# peripherals.net
KiCad netlist of a schematic drawn in Altium Designer
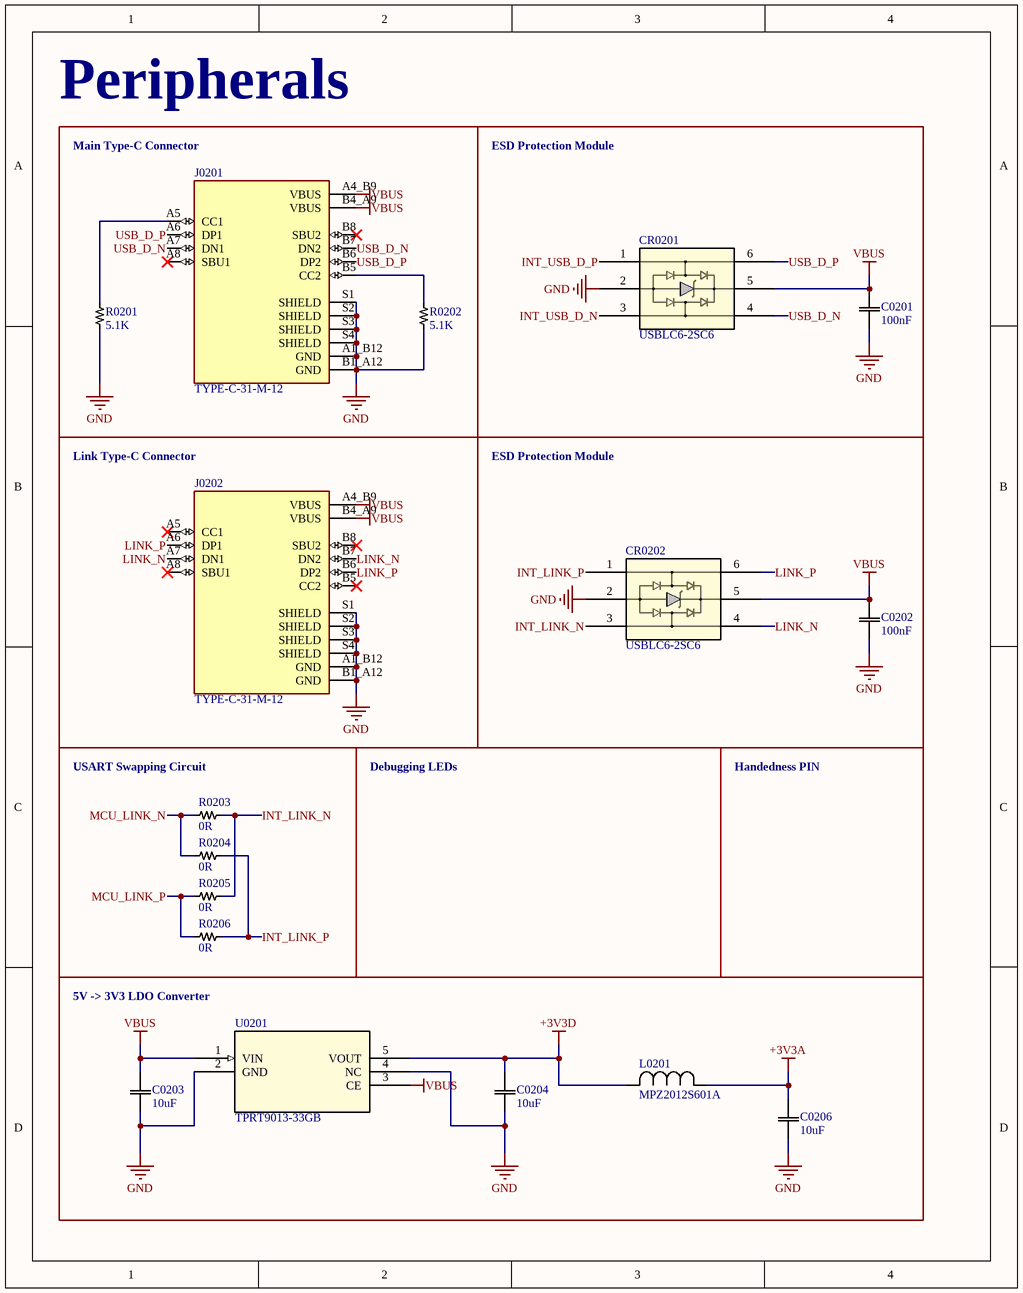
[diagram p0: peripherals.SchDoc]

(export (version "E")
  (design (tool "Eeschema 10.0.6"))
  (components
    (comp (ref "C0201")
      (value "100nF")
      (footprint "CAPC10555_55N_KEM")
      (description "SMD Comm X7R, Ceramic, SMD, MLCC, Temperature Stable, 0402")
      (fields
        (field (name "MANUFACTURER_PART_NUMBER") "C0402C104K4RACTU")
        (field (name "COPYRIGHT") "Copyright (C) 2025 Ultra Librarian. All rights reserved.")
      )
      (libsource (lib "SplitHE_Int") (part "C0402"))
    )
    (comp (ref "C0202")
      (value "100nF")
      (footprint "CAPC10555_55N_KEM")
      (description "SMD Comm X7R, Ceramic, SMD, MLCC, Temperature Stable, 0402")
      (fields
        (field (name "MANUFACTURER_PART_NUMBER") "C0402C104K4RACTU")
        (field (name "COPYRIGHT") "Copyright (C) 2025 Ultra Librarian. All rights reserved.")
      )
      (libsource (lib "SplitHE_Int") (part "C0402"))
    )
    (comp (ref "C0203")
      (value "10uF")
      (footprint "CAPC10555_55N_KEM")
      (description "SMD Comm X7R, Ceramic, SMD, MLCC, Temperature Stable, 0402")
      (fields
        (field (name "MANUFACTURER_PART_NUMBER") "C0402C104K4RACTU")
        (field (name "COPYRIGHT") "Copyright (C) 2025 Ultra Librarian. All rights reserved.")
      )
      (libsource (lib "SplitHE_Int") (part "C0402"))
    )
    (comp (ref "C0204")
      (value "10uF")
      (footprint "CAPC10555_55N_KEM")
      (description "SMD Comm X7R, Ceramic, SMD, MLCC, Temperature Stable, 0402")
      (fields
        (field (name "MANUFACTURER_PART_NUMBER") "C0402C104K4RACTU")
        (field (name "COPYRIGHT") "Copyright (C) 2025 Ultra Librarian. All rights reserved.")
      )
      (libsource (lib "SplitHE_Int") (part "C0402"))
    )
    (comp (ref "C0206")
      (value "10uF")
      (footprint "CAPC10555_55N_KEM")
      (description "SMD Comm X7R, Ceramic, SMD, MLCC, Temperature Stable, 0402")
      (fields
        (field (name "MANUFACTURER_PART_NUMBER") "C0402C104K4RACTU")
        (field (name "COPYRIGHT") "Copyright (C) 2025 Ultra Librarian. All rights reserved.")
      )
      (libsource (lib "SplitHE_Int") (part "C0402"))
    )
    (comp (ref "CR0201")
      (value "USBLC6-2SC6")
      (footprint "SOT23-6L_STM")
      (description "ESD Protection for USB 2.0 High Speed")
      (fields (field (name "COPYRIGHT") "Copyright (C) 2025 Ultra Librarian. All rights reserved."))
      (libsource (lib "SplitHE_Int") (part "USBLC6-2SC6"))
    )
    (comp (ref "CR0202")
      (value "USBLC6-2SC6")
      (footprint "SOT23-6L_STM")
      (description "ESD Protection for USB 2.0 High Speed")
      (fields (field (name "COPYRIGHT") "Copyright (C) 2025 Ultra Librarian. All rights reserved."))
      (libsource (lib "SplitHE_Int") (part "USBLC6-2SC6"))
    )
    (comp (ref "J0201")
      (value "TYPE-C-31-M-12")
      (footprint "HRO_TYPE-C-31-M-12")
      (description "USB Connectors 24 Receptacle 1 8.94*7.3mm RoHS")
      (fields (field (name "MF") "HRO Electronics Co., Ltd."))
      (libsource (lib "TYPE-C-31-M-12") (part "TYPE-C-31-M-12"))
    )
    (comp (ref "J0202")
      (value "TYPE-C-31-M-12")
      (footprint "HRO_TYPE-C-31-M-12")
      (description "USB Connectors 24 Receptacle 1 8.94*7.3mm RoHS")
      (fields (field (name "MF") "HRO Electronics Co., Ltd."))
      (libsource (lib "TYPE-C-31-M-12") (part "TYPE-C-31-M-12"))
    )
    (comp (ref "L0201")
      (value "MPZ2012S601A")
      (footprint "IND_MPZ2012_TDK")
      (description "No Description Available")
      (fields (field (name "COPYRIGHT") "Copyright (C) 2025 Ultra Librarian. All rights reserved."))
      (libsource (lib "SplitHE_Int") (part "MPZ2012S601A"))
    )
    (comp (ref "R0201")
      (value "5.1K")
      (footprint "RES0402_CPF_TYCO_TYC")
      (description "CPF 0402 RL")
      (fields
        (field (name "MANUFACTURER_PART_NUMBER") "CPF0402B33RE1")
        (field (name "COPYRIGHT") "Copyright (C) 2025 Ultra Librarian. All rights reserved.")
      )
      (libsource (lib "SplitHE_Int") (part "R0402"))
    )
    (comp (ref "R0202")
      (value "5.1K")
      (footprint "RES0402_CPF_TYCO_TYC")
      (description "CPF 0402 RL")
      (fields
        (field (name "MANUFACTURER_PART_NUMBER") "CPF0402B33RE1")
        (field (name "COPYRIGHT") "Copyright (C) 2025 Ultra Librarian. All rights reserved.")
      )
      (libsource (lib "SplitHE_Int") (part "R0402"))
    )
    (comp (ref "R0203")
      (value "0R")
      (footprint "RES0402_CPF_TYCO_TYC")
      (description "CPF 0402 RL")
      (fields
        (field (name "MANUFACTURER_PART_NUMBER") "CPF0402B33RE1")
        (field (name "COPYRIGHT") "Copyright (C) 2025 Ultra Librarian. All rights reserved.")
      )
      (libsource (lib "SplitHE_Int") (part "R0402"))
    )
    (comp (ref "R0204")
      (value "0R")
      (footprint "RES0402_CPF_TYCO_TYC")
      (description "CPF 0402 RL")
      (fields
        (field (name "MANUFACTURER_PART_NUMBER") "CPF0402B33RE1")
        (field (name "COPYRIGHT") "Copyright (C) 2025 Ultra Librarian. All rights reserved.")
      )
      (libsource (lib "SplitHE_Int") (part "R0402"))
    )
    (comp (ref "R0205")
      (value "0R")
      (footprint "RES0402_CPF_TYCO_TYC")
      (description "CPF 0402 RL")
      (fields
        (field (name "MANUFACTURER_PART_NUMBER") "CPF0402B33RE1")
        (field (name "COPYRIGHT") "Copyright (C) 2025 Ultra Librarian. All rights reserved.")
      )
      (libsource (lib "SplitHE_Int") (part "R0402"))
    )
    (comp (ref "R0206")
      (value "0R")
      (footprint "RES0402_CPF_TYCO_TYC")
      (description "CPF 0402 RL")
      (fields
        (field (name "MANUFACTURER_PART_NUMBER") "CPF0402B33RE1")
        (field (name "COPYRIGHT") "Copyright (C) 2025 Ultra Librarian. All rights reserved.")
      )
      (libsource (lib "SplitHE_Int") (part "R0402"))
    )
    (comp (ref "U0201")
      (value "TPRT9013-33GB")
      (footprint "SOT23-5_TCP")
      (description "No Description Available")
      (fields (field (name "COPYRIGHT") "Copyright (C) 2025 Ultra Librarian. All rights reserved."))
      (libsource (lib "SplitHE_Int") (part "TPRT9013-33GB"))
    )
  )
  (nets
    (net (code "1") (name "+3V3A") (class "Default")
      (node (ref "C0206") (pin "2") (pinfunction "2_2") (pintype "passive"))
      (node (ref "L0201") (pin "1") (pinfunction "1_1") (pintype "passive"))
    )
    (net (code "2") (name "+3V3D") (class "Default")
      (node (ref "C0204") (pin "2") (pinfunction "2_2") (pintype "passive"))
      (node (ref "L0201") (pin "2") (pinfunction "2_2") (pintype "passive"))
      (node (ref "U0201") (pin "5") (pinfunction "VOUT_5") (pintype "power_in"))
    )
    (net (code "3") (name "/INT_LINK_N") (class "Default")
      (node (ref "CR0202") (pin "3") (pinfunction "3_3") (pintype "passive"))
      (node (ref "R0203") (pin "1") (pinfunction "1_1") (pintype "passive"))
      (node (ref "R0205") (pin "1") (pinfunction "1_1") (pintype "passive"))
    )
    (net (code "4") (name "/INT_LINK_P") (class "Default")
      (node (ref "CR0202") (pin "1") (pinfunction "1_1") (pintype "passive"))
      (node (ref "R0204") (pin "1") (pinfunction "1_1") (pintype "passive"))
      (node (ref "R0206") (pin "1") (pinfunction "1_1") (pintype "passive"))
    )
    (net (code "5") (name "/INT_USB_D_N") (class "Default")
      (node (ref "CR0201") (pin "3") (pinfunction "3_3") (pintype "passive"))
    )
    (net (code "6") (name "/INT_USB_D_P") (class "Default")
      (node (ref "CR0201") (pin "1") (pinfunction "1_1") (pintype "passive"))
    )
    (net (code "7") (name "/LINK_N") (class "Default")
      (node (ref "CR0202") (pin "4") (pinfunction "4_4") (pintype "passive"))
      (node (ref "J0202") (pin "A7") (pinfunction "DN1_A7") (pintype "bidirectional"))
      (node (ref "J0202") (pin "B7") (pinfunction "DN2_B7") (pintype "bidirectional"))
    )
    (net (code "8") (name "/LINK_P") (class "Default")
      (node (ref "CR0202") (pin "6") (pinfunction "6_6") (pintype "passive"))
      (node (ref "J0202") (pin "A6") (pinfunction "DP1_A6") (pintype "bidirectional"))
      (node (ref "J0202") (pin "B6") (pinfunction "DP2_B6") (pintype "bidirectional"))
    )
    (net (code "9") (name "/MCU_LINK_N") (class "Default")
      (node (ref "R0203") (pin "2") (pinfunction "2_2") (pintype "passive"))
      (node (ref "R0204") (pin "2") (pinfunction "2_2") (pintype "passive"))
    )
    (net (code "10") (name "/MCU_LINK_P") (class "Default")
      (node (ref "R0205") (pin "2") (pinfunction "2_2") (pintype "passive"))
      (node (ref "R0206") (pin "2") (pinfunction "2_2") (pintype "passive"))
    )
    (net (code "11") (name "/USB_D_N") (class "Default")
      (node (ref "CR0201") (pin "4") (pinfunction "4_4") (pintype "passive"))
      (node (ref "J0201") (pin "A7") (pinfunction "DN1_A7") (pintype "bidirectional"))
      (node (ref "J0201") (pin "B7") (pinfunction "DN2_B7") (pintype "bidirectional"))
    )
    (net (code "12") (name "/USB_D_P") (class "Default")
      (node (ref "CR0201") (pin "6") (pinfunction "6_6") (pintype "passive"))
      (node (ref "J0201") (pin "A6") (pinfunction "DP1_A6") (pintype "bidirectional"))
      (node (ref "J0201") (pin "B6") (pinfunction "DP2_B6") (pintype "bidirectional"))
    )
    (net (code "13") (name "GND") (class "Default")
      (node (ref "C0201") (pin "1") (pinfunction "1_1") (pintype "passive"))
      (node (ref "C0202") (pin "1") (pinfunction "1_1") (pintype "passive"))
      (node (ref "C0203") (pin "1") (pinfunction "1_1") (pintype "passive"))
      (node (ref "C0204") (pin "1") (pinfunction "1_1") (pintype "passive"))
      (node (ref "C0206") (pin "1") (pinfunction "1_1") (pintype "passive"))
      (node (ref "CR0201") (pin "2") (pinfunction "2_2") (pintype "passive"))
      (node (ref "CR0202") (pin "2") (pinfunction "2_2") (pintype "passive"))
      (node (ref "J0201") (pin "A1_B12") (pinfunction "GND_A1_B12") (pintype "power_in"))
      (node (ref "J0201") (pin "B1_A12") (pinfunction "GND_B1_A12") (pintype "power_in"))
      (node (ref "J0201") (pin "S1") (pinfunction "SHIELD_S1") (pintype "passive"))
      (node (ref "J0201") (pin "S2") (pinfunction "SHIELD_S2") (pintype "passive"))
      (node (ref "J0201") (pin "S3") (pinfunction "SHIELD_S3") (pintype "passive"))
      (node (ref "J0201") (pin "S4") (pinfunction "SHIELD_S4") (pintype "passive"))
      (node (ref "J0202") (pin "A1_B12") (pinfunction "GND_A1_B12") (pintype "power_in"))
      (node (ref "J0202") (pin "B1_A12") (pinfunction "GND_B1_A12") (pintype "power_in"))
      (node (ref "J0202") (pin "S1") (pinfunction "SHIELD_S1") (pintype "passive"))
      (node (ref "J0202") (pin "S2") (pinfunction "SHIELD_S2") (pintype "passive"))
      (node (ref "J0202") (pin "S3") (pinfunction "SHIELD_S3") (pintype "passive"))
      (node (ref "J0202") (pin "S4") (pinfunction "SHIELD_S4") (pintype "passive"))
      (node (ref "R0201") (pin "1") (pinfunction "1_1") (pintype "passive"))
      (node (ref "R0202") (pin "1") (pinfunction "1_1") (pintype "passive"))
      (node (ref "U0201") (pin "2") (pinfunction "GND_2") (pintype "power_in"))
      (node (ref "U0201") (pin "4") (pinfunction "NC_4") (pintype "passive"))
    )
    (net (code "14") (name "Net-(J0201-CC1)") (class "Default")
      (node (ref "J0201") (pin "A5") (pinfunction "CC1_A5") (pintype "bidirectional"))
      (node (ref "R0201") (pin "2") (pinfunction "2_2") (pintype "passive"))
    )
    (net (code "15") (name "Net-(J0201-CC2)") (class "Default")
      (node (ref "J0201") (pin "B5") (pinfunction "CC2_B5") (pintype "bidirectional"))
      (node (ref "R0202") (pin "2") (pinfunction "2_2") (pintype "passive"))
    )
    (net (code "16") (name "VBUS") (class "Default")
      (node (ref "C0201") (pin "2") (pinfunction "2_2") (pintype "passive"))
      (node (ref "C0202") (pin "2") (pinfunction "2_2") (pintype "passive"))
      (node (ref "C0203") (pin "2") (pinfunction "2_2") (pintype "passive"))
      (node (ref "CR0201") (pin "5") (pinfunction "5_5") (pintype "passive"))
      (node (ref "CR0202") (pin "5") (pinfunction "5_5") (pintype "passive"))
      (node (ref "J0201") (pin "A4_B9") (pinfunction "VBUS_A4_B9") (pintype "power_in"))
      (node (ref "J0201") (pin "B4_A9") (pinfunction "VBUS_B4_A9") (pintype "power_in"))
      (node (ref "J0202") (pin "A4_B9") (pinfunction "VBUS_A4_B9") (pintype "power_in"))
      (node (ref "J0202") (pin "B4_A9") (pinfunction "VBUS_B4_A9") (pintype "power_in"))
      (node (ref "U0201") (pin "1") (pinfunction "VIN_1") (pintype "input"))
      (node (ref "U0201") (pin "3") (pinfunction "CE_3") (pintype "passive"))
    )
    (net (code "17") (name "unconnected-(J0201-SBU1-PadA8)") (class "Default")
      (node (ref "J0201") (pin "A8") (pinfunction "SBU1_A8") (pintype "bidirectional+no_connect"))
    )
    (net (code "18") (name "unconnected-(J0201-SBU2-PadB8)") (class "Default")
      (node (ref "J0201") (pin "B8") (pinfunction "SBU2_B8") (pintype "bidirectional+no_connect"))
    )
    (net (code "19") (name "unconnected-(J0202-CC1-PadA5)") (class "Default")
      (node (ref "J0202") (pin "A5") (pinfunction "CC1_A5") (pintype "bidirectional+no_connect"))
    )
    (net (code "20") (name "unconnected-(J0202-CC2-PadB5)") (class "Default")
      (node (ref "J0202") (pin "B5") (pinfunction "CC2_B5") (pintype "bidirectional+no_connect"))
    )
    (net (code "21") (name "unconnected-(J0202-SBU1-PadA8)") (class "Default")
      (node (ref "J0202") (pin "A8") (pinfunction "SBU1_A8") (pintype "bidirectional+no_connect"))
    )
    (net (code "22") (name "unconnected-(J0202-SBU2-PadB8)") (class "Default")
      (node (ref "J0202") (pin "B8") (pinfunction "SBU2_B8") (pintype "bidirectional+no_connect"))
    )
  )
)
